# RGB_Video_Output.net
KiCad netlist of a schematic drawn in Altium Designer
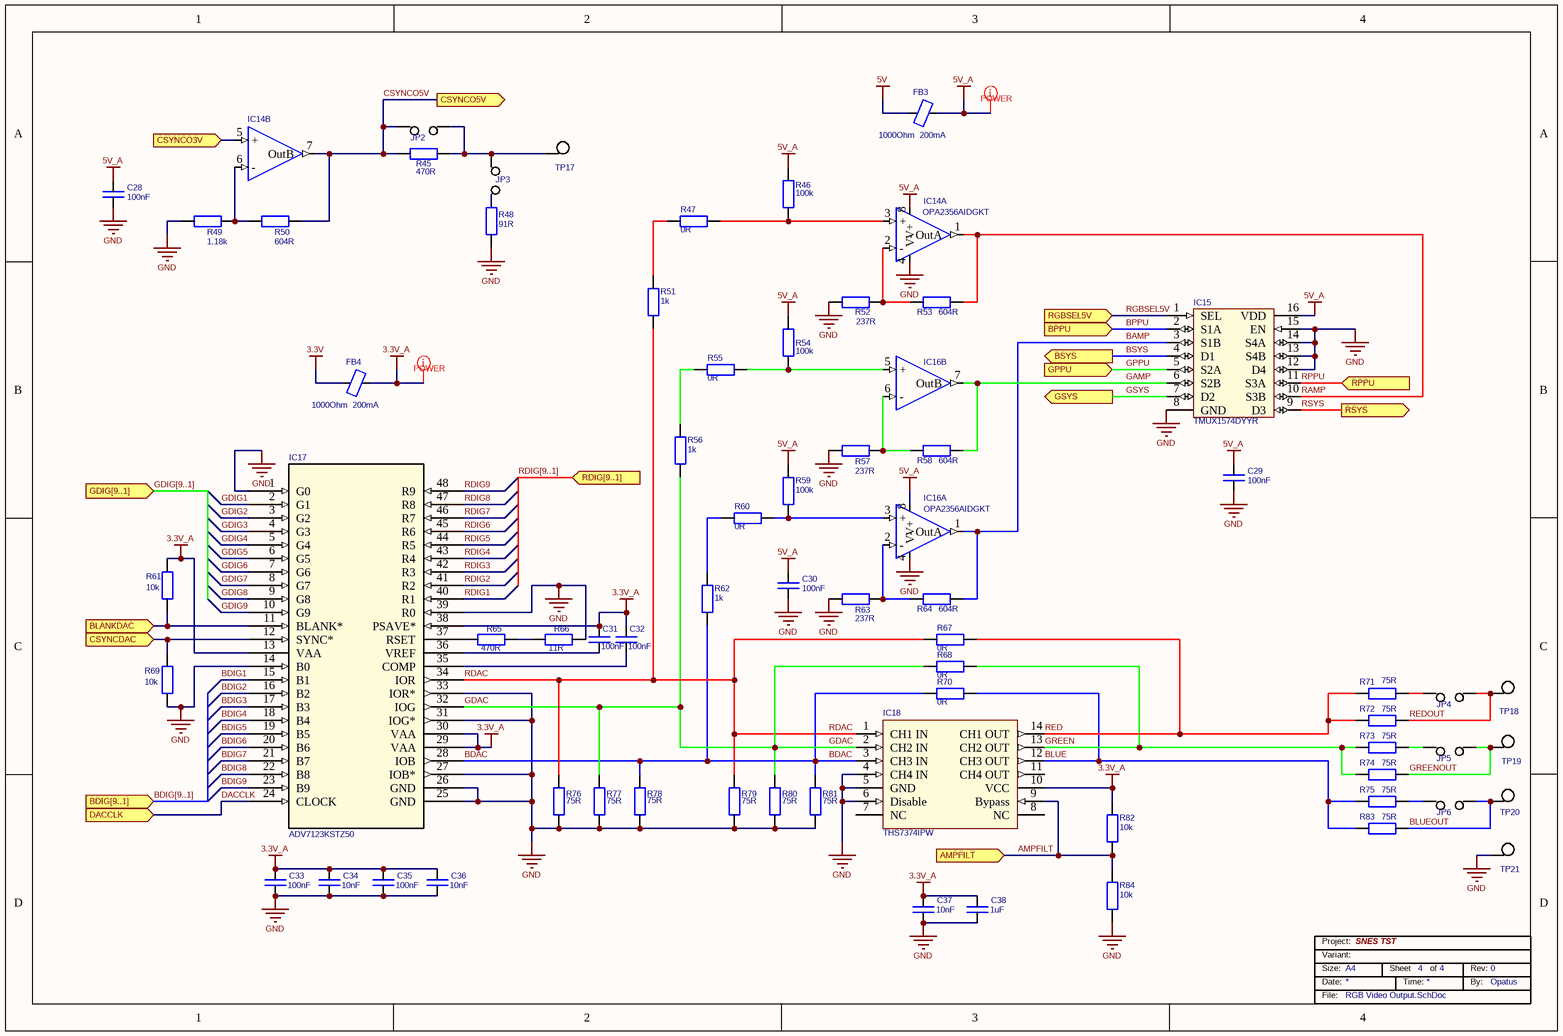
[diagram p0: RGB Video Output.SchDoc]

(export (version "E")
  (design (tool "Eeschema 10.0.6"))
  (components
    (comp (ref "C28")
      (value "100nF")
      (footprint "Cap_0402_Chip")
      (fields
        (field (name "TOLERANCE") "±20%")
        (field (name "Comment") "Ceramic Capacitor 100nF 10V ±20% X7R 0402")
      )
      (libsource (lib "PCB") (part "Capacitor"))
    )
    (comp (ref "C29")
      (value "100nF")
      (footprint "Cap_0402_Chip")
      (fields
        (field (name "TOLERANCE") "±20%")
        (field (name "Comment") "Ceramic Capacitor 100nF 10V ±20% X7R 0402")
      )
      (libsource (lib "PCB") (part "Capacitor"))
    )
    (comp (ref "C30")
      (value "100nF")
      (footprint "Cap_0402_Chip")
      (fields
        (field (name "TOLERANCE") "±20%")
        (field (name "Comment") "Ceramic Capacitor 100nF 10V ±20% X7R 0402")
      )
      (libsource (lib "PCB") (part "Capacitor"))
    )
    (comp (ref "C31")
      (value "100nF")
      (footprint "Cap_0402_Chip")
      (fields
        (field (name "TOLERANCE") "±20%")
        (field (name "Comment") "Ceramic Capacitor 100nF 10V ±20% X7R 0402")
      )
      (libsource (lib "PCB") (part "Capacitor"))
    )
    (comp (ref "C32")
      (value "100nF")
      (footprint "Cap_0402_Chip")
      (fields
        (field (name "TOLERANCE") "±20%")
        (field (name "Comment") "Ceramic Capacitor 100nF 10V ±20% X7R 0402")
      )
      (libsource (lib "PCB") (part "Capacitor"))
    )
    (comp (ref "C33")
      (value "100nF")
      (footprint "Cap_0402_Chip")
      (fields
        (field (name "TOLERANCE") "±20%")
        (field (name "Comment") "Ceramic Capacitor 100nF 10V ±20% X7R 0402")
      )
      (libsource (lib "PCB") (part "Capacitor"))
    )
    (comp (ref "C34")
      (value "10nF")
      (footprint "Cap_0402_Chip")
      (fields
        (field (name "TOLERANCE") "±20%")
        (field (name "Comment") "Ceramic Capacitor 10nF 10V ±20% X7R 0402")
      )
      (libsource (lib "PCB") (part "Capacitor"))
    )
    (comp (ref "C35")
      (value "100nF")
      (footprint "Cap_0402_Chip")
      (fields
        (field (name "TOLERANCE") "±20%")
        (field (name "Comment") "Ceramic Capacitor 100nF 10V ±20% X7R 0402")
      )
      (libsource (lib "PCB") (part "Capacitor"))
    )
    (comp (ref "C36")
      (value "10nF")
      (footprint "Cap_0402_Chip")
      (fields
        (field (name "TOLERANCE") "±20%")
        (field (name "Comment") "Ceramic Capacitor 10nF 10V ±20% X7R 0402")
      )
      (libsource (lib "PCB") (part "Capacitor"))
    )
    (comp (ref "C37")
      (value "10nF")
      (footprint "Cap_0402_Chip")
      (fields
        (field (name "TOLERANCE") "±20%")
        (field (name "Comment") "Ceramic Capacitor 10nF 10V ±20% X7R 0402")
      )
      (libsource (lib "PCB") (part "Capacitor"))
    )
    (comp (ref "C38")
      (value "1uF")
      (footprint "Cap_0603_Chip")
      (fields
        (field (name "TOLERANCE") "±20%")
        (field (name "Comment") "Ceramic Capacitor 1uF 10V ±20% X7R 0603")
      )
      (libsource (lib "PCB") (part "Capacitor"))
    )
    (comp (ref "FB3")
      (value "1000Ohm  200mA")
      (footprint "Ind_0402_Chip")
      (fields (field (name "MANUFACTURER_PART_NUMBER") "MMZ1005S102CT000"))
      (libsource (lib "PCB") (part "Ferrite Bead"))
    )
    (comp (ref "FB4")
      (value "1000Ohm  200mA")
      (footprint "Ind_0402_Chip")
      (fields (field (name "MANUFACTURER_PART_NUMBER") "MMZ1005S102CT000"))
      (libsource (lib "PCB") (part "Ferrite Bead"))
    )
    (comp (ref "IC14")
      (value "OPA2356")
      (footprint "MSOP8")
      (fields (field (name "MANUFACTURER_PART_NUMBER") "OPA2356AIDGKT"))
      (libsource (lib "PCB") (part "OPA2356"))
    )
    (comp (ref "IC15")
      (value "TMUX1574")
      (footprint "SOT-23THIN16")
      (description "SPDT 4 Ch")
      (fields (field (name "MANUFACTURER_PART_NUMBER") "TMUX1574DYYR"))
      (libsource (lib "PCB") (part "TMUX1574"))
    )
    (comp (ref "IC16")
      (value "OPA2356")
      (footprint "MSOP8")
      (fields (field (name "MANUFACTURER_PART_NUMBER") "OPA2356AIDGKT"))
      (libsource (lib "PCB") (part "OPA2356"))
    )
    (comp (ref "IC17")
      (value "ADV7123")
      (footprint "ST_48_ADI")
      (description "10Bit Video DAC")
      (fields
        (field (name "MANUFACTURER_PART_NUMBER") "ADV7123KSTZ50")
        (field (name "COPYRIGHT") "Copyright (C) 2018 Accelerated Designs. All rights reserved")
      )
      (libsource (lib "PCB") (part "ADV7123KSTZ140"))
    )
    (comp (ref "IC18")
      (value "THS7374")
      (footprint "TSSOP14")
      (fields (field (name "MANUFACTURER_PART_NUMBER") "THS7374IPW"))
      (libsource (lib "PCB") (part "THS7374"))
    )
    (comp (ref "JP2") (value "Jumper") (footprint "Jumper") (libsource (lib "PCB") (part "Jumper")))
    (comp (ref "JP3") (value "Jumper") (footprint "Jumper") (libsource (lib "PCB") (part "Jumper")))
    (comp (ref "JP4") (value "Jumper") (footprint "Jumper") (libsource (lib "PCB") (part "Jumper")))
    (comp (ref "JP5") (value "Jumper") (footprint "Jumper") (libsource (lib "PCB") (part "Jumper")))
    (comp (ref "JP6") (value "Jumper") (footprint "Jumper") (libsource (lib "PCB") (part "Jumper")))
    (comp (ref "R45")
      (value "470R")
      (footprint "Res_0603_Chip")
      (fields (field (name "TOLERANCE") "±1%") (field (name "Comment") "Resistor 470R 0603 ±1%"))
      (libsource (lib "") (part "R_3"))
    )
    (comp (ref "R46")
      (value "100k")
      (footprint "Res_0402_Chip")
      (fields (field (name "TOLERANCE") "±1%") (field (name "Comment") "Resistor 100k 0402 ±1%"))
      (libsource (lib "") (part "R_1"))
    )
    (comp (ref "R47")
      (value "0R")
      (footprint "Res_0402_Chip")
      (fields (field (name "Comment") "Resistor 0R 0402 "))
      (libsource (lib "PCB") (part "R"))
    )
    (comp (ref "R48")
      (value "91R")
      (footprint "Res_0603_Chip")
      (fields (field (name "TOLERANCE") "±1%") (field (name "Comment") "Resistor 91R 0603 ±1%"))
      (libsource (lib "") (part "R_1"))
    )
    (comp (ref "R49")
      (value "1.18k")
      (footprint "Res_0402_Chip")
      (fields (field (name "TOLERANCE") "±1%") (field (name "Comment") "Resistor 1.18k 0402 ±1%"))
      (libsource (lib "") (part "R_3"))
    )
    (comp (ref "R50")
      (value "604R")
      (footprint "Res_0402_Chip")
      (fields (field (name "TOLERANCE") "±1%") (field (name "Comment") "Resistor 604R 0402 ±1%"))
      (libsource (lib "PCB") (part "R"))
    )
    (comp (ref "R51")
      (value "1k")
      (footprint "Res_0402_Chip")
      (fields (field (name "TOLERANCE") "±1%") (field (name "Comment") "Resistor 1k 0402 ±1%"))
      (libsource (lib "") (part "R_2"))
    )
    (comp (ref "R52")
      (value "237R")
      (footprint "Res_0402_Chip")
      (fields (field (name "TOLERANCE") "±1%") (field (name "Comment") "Resistor 237R 0402 ±1%"))
      (libsource (lib "") (part "R_3"))
    )
    (comp (ref "R53")
      (value "604R")
      (footprint "Res_0402_Chip")
      (fields (field (name "TOLERANCE") "±1%") (field (name "Comment") "Resistor 604R 0402 ±1%"))
      (libsource (lib "") (part "R_3"))
    )
    (comp (ref "R54")
      (value "100k")
      (footprint "Res_0402_Chip")
      (fields (field (name "TOLERANCE") "±1%") (field (name "Comment") "Resistor 100k 0402 ±1%"))
      (libsource (lib "") (part "R_1"))
    )
    (comp (ref "R55")
      (value "0R")
      (footprint "Res_0402_Chip")
      (fields (field (name "Comment") "Resistor 0R 0402 "))
      (libsource (lib "PCB") (part "R"))
    )
    (comp (ref "R56")
      (value "1k")
      (footprint "Res_0402_Chip")
      (fields (field (name "TOLERANCE") "±1%") (field (name "Comment") "Resistor 1k 0402 ±1%"))
      (libsource (lib "") (part "R_2"))
    )
    (comp (ref "R57")
      (value "237R")
      (footprint "Res_0402_Chip")
      (fields (field (name "TOLERANCE") "±1%") (field (name "Comment") "Resistor 237R 0402 ±1%"))
      (libsource (lib "") (part "R_3"))
    )
    (comp (ref "R58")
      (value "604R")
      (footprint "Res_0402_Chip")
      (fields (field (name "TOLERANCE") "±1%") (field (name "Comment") "Resistor 604R 0402 ±1%"))
      (libsource (lib "PCB") (part "R"))
    )
    (comp (ref "R59")
      (value "100k")
      (footprint "Res_0402_Chip")
      (fields (field (name "TOLERANCE") "±1%") (field (name "Comment") "Resistor 100k 0402 ±1%"))
      (libsource (lib "") (part "R_1"))
    )
    (comp (ref "R60")
      (value "0R")
      (footprint "Res_0402_Chip")
      (fields (field (name "Comment") "Resistor 0R 0402 "))
      (libsource (lib "PCB") (part "R"))
    )
    (comp (ref "R61")
      (value "10k")
      (footprint "Res_0402_Chip")
      (fields (field (name "TOLERANCE") "±1%") (field (name "Comment") "Resistor 10k 0402 ±1%"))
      (libsource (lib "") (part "R_1"))
    )
    (comp (ref "R62")
      (value "1k")
      (footprint "Res_0402_Chip")
      (fields (field (name "TOLERANCE") "±1%") (field (name "Comment") "Resistor 1k 0402 ±1%"))
      (libsource (lib "") (part "R_2"))
    )
    (comp (ref "R63")
      (value "237R")
      (footprint "Res_0402_Chip")
      (fields (field (name "TOLERANCE") "±1%") (field (name "Comment") "Resistor 237R 0402 ±1%"))
      (libsource (lib "PCB") (part "R"))
    )
    (comp (ref "R64")
      (value "604R")
      (footprint "Res_0402_Chip")
      (fields (field (name "TOLERANCE") "±1%") (field (name "Comment") "Resistor 604R 0402 ±1%"))
      (libsource (lib "") (part "R_3"))
    )
    (comp (ref "R65")
      (value "470R")
      (footprint "Res_0402_Chip")
      (fields (field (name "TOLERANCE") "±1%") (field (name "Comment") "Resistor 470R 0402 ±1%"))
      (libsource (lib "") (part "R_3"))
    )
    (comp (ref "R66")
      (value "11R")
      (footprint "Res_0402_Chip")
      (fields (field (name "TOLERANCE") "±1%") (field (name "Comment") "Resistor 11R 0402 ±1%"))
      (libsource (lib "") (part "R_3"))
    )
    (comp (ref "R67")
      (value "0R")
      (footprint "Res_0402_Chip")
      (fields (field (name "Comment") "Resistor 0R 0402 "))
      (libsource (lib "PCB") (part "R"))
    )
    (comp (ref "R68")
      (value "0R")
      (footprint "Res_0402_Chip")
      (fields (field (name "Comment") "Resistor 0R 0402 "))
      (libsource (lib "PCB") (part "R"))
    )
    (comp (ref "R69")
      (value "10k")
      (footprint "Res_0402_Chip")
      (fields (field (name "TOLERANCE") "±1%") (field (name "Comment") "Resistor 10k 0402 ±1%"))
      (libsource (lib "") (part "R_1"))
    )
    (comp (ref "R70")
      (value "0R")
      (footprint "Res_0402_Chip")
      (fields (field (name "Comment") "Resistor 0R 0402 "))
      (libsource (lib "PCB") (part "R"))
    )
    (comp (ref "R71")
      (value "75R")
      (footprint "Res_0603_Chip")
      (fields (field (name "TOLERANCE") "±1%") (field (name "Comment") "Resistor 75R 0603 ±1%"))
      (libsource (lib "") (part "R_3"))
    )
    (comp (ref "R72")
      (value "75R")
      (footprint "Res_0603_Chip")
      (fields (field (name "TOLERANCE") "±1%") (field (name "Comment") "Resistor 75R 0603 ±1%"))
      (libsource (lib "") (part "R_3"))
    )
    (comp (ref "R73")
      (value "75R")
      (footprint "Res_0603_Chip")
      (fields (field (name "TOLERANCE") "±1%") (field (name "Comment") "Resistor 75R 0603 ±1%"))
      (libsource (lib "") (part "R_3"))
    )
    (comp (ref "R74")
      (value "75R")
      (footprint "Res_0603_Chip")
      (fields (field (name "TOLERANCE") "±1%") (field (name "Comment") "Resistor 75R 0603 ±1%"))
      (libsource (lib "") (part "R_3"))
    )
    (comp (ref "R75")
      (value "75R")
      (footprint "Res_0603_Chip")
      (fields (field (name "TOLERANCE") "±1%") (field (name "Comment") "Resistor 75R 0603 ±1%"))
      (libsource (lib "") (part "R_3"))
    )
    (comp (ref "R76")
      (value "75R")
      (footprint "Res_0402_Chip")
      (fields (field (name "TOLERANCE") "±1%") (field (name "Comment") "Resistor 75R 0402 ±1%"))
      (libsource (lib "") (part "R_1"))
    )
    (comp (ref "R77")
      (value "75R")
      (footprint "Res_0402_Chip")
      (fields (field (name "TOLERANCE") "±1%") (field (name "Comment") "Resistor 75R 0402 ±1%"))
      (libsource (lib "") (part "R_1"))
    )
    (comp (ref "R78")
      (value "75R")
      (footprint "Res_0402_Chip")
      (fields (field (name "TOLERANCE") "±1%") (field (name "Comment") "Resistor 75R 0402 ±1%"))
      (libsource (lib "") (part "R_1"))
    )
    (comp (ref "R79")
      (value "75R")
      (footprint "Res_0402_Chip")
      (fields (field (name "TOLERANCE") "±1%") (field (name "Comment") "Resistor 75R 0402 ±1%"))
      (libsource (lib "") (part "R_1"))
    )
    (comp (ref "R80")
      (value "75R")
      (footprint "Res_0402_Chip")
      (fields (field (name "TOLERANCE") "±1%") (field (name "Comment") "Resistor 75R 0402 ±1%"))
      (libsource (lib "") (part "R_1"))
    )
    (comp (ref "R81")
      (value "75R")
      (footprint "Res_0402_Chip")
      (fields (field (name "TOLERANCE") "±1%") (field (name "Comment") "Resistor 75R 0402 ±1%"))
      (libsource (lib "") (part "R_1"))
    )
    (comp (ref "R82")
      (value "10k")
      (footprint "Res_0402_Chip")
      (fields (field (name "TOLERANCE") "±1%") (field (name "Comment") "Resistor 10k 0402 ±1%"))
      (libsource (lib "") (part "R_2"))
    )
    (comp (ref "R83")
      (value "75R")
      (footprint "Res_0603_Chip")
      (fields (field (name "TOLERANCE") "±1%") (field (name "Comment") "Resistor 75R 0603 ±1%"))
      (libsource (lib "") (part "R_3"))
    )
    (comp (ref "R84")
      (value "10k")
      (footprint "Res_0402_Chip")
      (fields (field (name "TOLERANCE") "±1%") (field (name "Comment") "Resistor 10k 0402 ±1%"))
      (libsource (lib "") (part "R_2"))
    )
    (comp (ref "TP17")
      (value "Pin Connector")
      (footprint "Pin Connector Small")
      (libsource (lib "PCB") (part "Pin Connector"))
    )
    (comp (ref "TP18")
      (value "Pin Connector")
      (footprint "Pin Connector Small")
      (libsource (lib "PCB") (part "Pin Connector"))
    )
    (comp (ref "TP19")
      (value "Pin Connector")
      (footprint "Pin Connector Small")
      (libsource (lib "PCB") (part "Pin Connector"))
    )
    (comp (ref "TP20")
      (value "Pin Connector")
      (footprint "Pin Connector Small")
      (libsource (lib "PCB") (part "Pin Connector"))
    )
    (comp (ref "TP21")
      (value "Pin Connector")
      (footprint "Pin Connector Small")
      (libsource (lib "PCB") (part "Pin Connector"))
    )
  )
  (nets
    (net (code "1") (name "/AMPFILT") (class "Default")
      (node (ref "IC18") (pin "9") (pinfunction "Bypass_9") (pintype "input"))
      (node (ref "R82") (pin "2") (pintype "passive"))
      (node (ref "R84") (pin "1") (pintype "passive"))
    )
    (net (code "2") (name "/BAMP") (class "Default")
      (node (ref "IC15") (pin "3") (pinfunction "S1B_3") (pintype "bidirectional"))
      (node (ref "IC16") (pin "1") (pinfunction "OutA_1") (pintype "output"))
      (node (ref "R64") (pin "2") (pintype "passive"))
    )
    (net (code "3") (name "/BDAC") (class "Default")
      (node (ref "IC17") (pin "28") (pinfunction "IOB_28") (pintype "output"))
      (node (ref "IC18") (pin "3") (pinfunction "CH3_IN_3") (pintype "input"))
      (node (ref "R62") (pin "2") (pintype "passive"))
      (node (ref "R70") (pin "2") (pintype "passive"))
      (node (ref "R78") (pin "2") (pintype "passive"))
      (node (ref "R81") (pin "2") (pintype "passive"))
    )
    (net (code "4") (name "/BDIG1") (class "Default")
      (node (ref "IC17") (pin "15") (pinfunction "B1_15") (pintype "input"))
    )
    (net (code "5") (name "/BDIG2") (class "Default")
      (node (ref "IC17") (pin "16") (pinfunction "B2_16") (pintype "input"))
    )
    (net (code "6") (name "/BDIG3") (class "Default")
      (node (ref "IC17") (pin "17") (pinfunction "B3_17") (pintype "input"))
    )
    (net (code "7") (name "/BDIG4") (class "Default")
      (node (ref "IC17") (pin "18") (pinfunction "B4_18") (pintype "input"))
    )
    (net (code "8") (name "/BDIG5") (class "Default")
      (node (ref "IC17") (pin "19") (pinfunction "B5_19") (pintype "input"))
    )
    (net (code "9") (name "/BDIG6") (class "Default")
      (node (ref "IC17") (pin "20") (pinfunction "B6_20") (pintype "input"))
    )
    (net (code "10") (name "/BDIG7") (class "Default")
      (node (ref "IC17") (pin "21") (pinfunction "B7_21") (pintype "input"))
    )
    (net (code "11") (name "/BDIG8") (class "Default")
      (node (ref "IC17") (pin "22") (pinfunction "B8_22") (pintype "input"))
    )
    (net (code "12") (name "/BDIG9") (class "Default")
      (node (ref "IC17") (pin "23") (pinfunction "B9_23") (pintype "input"))
    )
    (net (code "14") (name "/BLANKDAC") (class "Default")
      (node (ref "IC17") (pin "11") (pinfunction "BLANK*_11") (pintype "input"))
      (node (ref "R61") (pin "1") (pintype "passive"))
    )
    (net (code "15") (name "/BLUE") (class "Default")
      (node (ref "IC18") (pin "12") (pinfunction "CH3_OUT_12") (pintype "output"))
      (node (ref "R70") (pin "1") (pintype "passive"))
      (node (ref "R75") (pin "1") (pintype "passive"))
      (node (ref "R83") (pin "1") (pintype "passive"))
    )
    (net (code "16") (name "/BLUEOUT") (class "Default")
      (node (ref "JP6") (pin "1") (pinfunction "0_1") (pintype "passive"))
      (node (ref "R83") (pin "2") (pintype "passive"))
      (node (ref "TP20") (pin "1") (pinfunction "0_1") (pintype "passive"))
    )
    (net (code "17") (name "/BPPU") (class "Default")
      (node (ref "IC15") (pin "2") (pinfunction "S1A_2") (pintype "bidirectional"))
    )
    (net (code "18") (name "/BSYS") (class "Default")
      (node (ref "IC15") (pin "4") (pinfunction "D1_4") (pintype "bidirectional"))
    )
    (net (code "19") (name "/CSYNCDAC") (class "Default")
      (node (ref "IC17") (pin "12") (pinfunction "SYNC*_12") (pintype "input"))
      (node (ref "R69") (pin "2") (pintype "passive"))
    )
    (net (code "20") (name "/CSYNCO3V") (class "Default")
      (node (ref "IC14") (pin "5") (pinfunction "+_5") (pintype "input"))
    )
    (net (code "21") (name "/CSYNCO5V") (class "Default")
      (node (ref "IC14") (pin "7") (pinfunction "OutB_7") (pintype "output"))
      (node (ref "JP2") (pin "2") (pinfunction "0_2") (pintype "passive"))
      (node (ref "R45") (pin "1") (pintype "passive"))
      (node (ref "R50") (pin "1") (pintype "passive"))
    )
    (net (code "22") (name "/DACCLK") (class "Default")
      (node (ref "IC17") (pin "24") (pinfunction "CLOCK_24") (pintype "input"))
    )
    (net (code "23") (name "/GAMP") (class "Default")
      (node (ref "IC15") (pin "6") (pinfunction "S2B_6") (pintype "bidirectional"))
      (node (ref "IC16") (pin "7") (pinfunction "OutB_7") (pintype "output"))
      (node (ref "R58") (pin "1") (pintype "passive"))
    )
    (net (code "24") (name "/GDAC") (class "Default")
      (node (ref "IC17") (pin "32") (pinfunction "IOG_32") (pintype "output"))
      (node (ref "IC18") (pin "2") (pinfunction "CH2_IN_2") (pintype "input"))
      (node (ref "R56") (pin "2") (pintype "passive"))
      (node (ref "R68") (pin "2") (pintype "passive"))
      (node (ref "R77") (pin "2") (pintype "passive"))
      (node (ref "R80") (pin "2") (pintype "passive"))
    )
    (net (code "25") (name "/GDIG1") (class "Default")
      (node (ref "IC17") (pin "2") (pinfunction "G1_2") (pintype "input"))
    )
    (net (code "26") (name "/GDIG2") (class "Default")
      (node (ref "IC17") (pin "3") (pinfunction "G2_3") (pintype "input"))
    )
    (net (code "27") (name "/GDIG3") (class "Default")
      (node (ref "IC17") (pin "4") (pinfunction "G3_4") (pintype "input"))
    )
    (net (code "28") (name "/GDIG4") (class "Default")
      (node (ref "IC17") (pin "5") (pinfunction "G4_5") (pintype "input"))
    )
    (net (code "29") (name "/GDIG5") (class "Default")
      (node (ref "IC17") (pin "6") (pinfunction "G5_6") (pintype "input"))
    )
    (net (code "30") (name "/GDIG6") (class "Default")
      (node (ref "IC17") (pin "7") (pinfunction "G6_7") (pintype "input"))
    )
    (net (code "31") (name "/GDIG7") (class "Default")
      (node (ref "IC17") (pin "8") (pinfunction "G7_8") (pintype "input"))
    )
    (net (code "32") (name "/GDIG8") (class "Default")
      (node (ref "IC17") (pin "9") (pinfunction "G8_9") (pintype "input"))
    )
    (net (code "33") (name "/GDIG9") (class "Default")
      (node (ref "IC17") (pin "10") (pinfunction "G9_10") (pintype "input"))
    )
    (net (code "35") (name "/GPPU") (class "Default")
      (node (ref "IC15") (pin "5") (pinfunction "S2A_5") (pintype "bidirectional"))
    )
    (net (code "36") (name "/GREEN") (class "Default")
      (node (ref "IC18") (pin "13") (pinfunction "CH2_OUT_13") (pintype "output"))
      (node (ref "R68") (pin "1") (pintype "passive"))
      (node (ref "R73") (pin "1") (pintype "passive"))
      (node (ref "R74") (pin "1") (pintype "passive"))
    )
    (net (code "37") (name "/GREENOUT") (class "Default")
      (node (ref "JP5") (pin "1") (pinfunction "0_1") (pintype "passive"))
      (node (ref "R74") (pin "2") (pintype "passive"))
      (node (ref "TP19") (pin "1") (pinfunction "0_1") (pintype "passive"))
    )
    (net (code "38") (name "/GSYS") (class "Default")
      (node (ref "IC15") (pin "7") (pinfunction "D2_7") (pintype "bidirectional"))
    )
    (net (code "39") (name "/RAMP") (class "Default")
      (node (ref "IC14") (pin "1") (pinfunction "OutA_1") (pintype "output"))
      (node (ref "IC15") (pin "10") (pinfunction "S3B_10") (pintype "bidirectional"))
      (node (ref "R53") (pin "2") (pintype "passive"))
    )
    (net (code "40") (name "/RDAC") (class "Default")
      (node (ref "IC17") (pin "34") (pinfunction "IOR_34") (pintype "output"))
      (node (ref "IC18") (pin "1") (pinfunction "CH1_IN_1") (pintype "input"))
      (node (ref "R51") (pin "2") (pintype "passive"))
      (node (ref "R67") (pin "2") (pintype "passive"))
      (node (ref "R76") (pin "2") (pintype "passive"))
      (node (ref "R79") (pin "2") (pintype "passive"))
    )
    (net (code "41") (name "/RDIG1") (class "Default")
      (node (ref "IC17") (pin "40") (pinfunction "R1_40") (pintype "input"))
    )
    (net (code "42") (name "/RDIG2") (class "Default")
      (node (ref "IC17") (pin "41") (pinfunction "R2_41") (pintype "input"))
    )
    (net (code "43") (name "/RDIG3") (class "Default")
      (node (ref "IC17") (pin "42") (pinfunction "R3_42") (pintype "input"))
    )
    (net (code "44") (name "/RDIG4") (class "Default")
      (node (ref "IC17") (pin "43") (pinfunction "R4_43") (pintype "input"))
    )
    (net (code "45") (name "/RDIG5") (class "Default")
      (node (ref "IC17") (pin "44") (pinfunction "R5_44") (pintype "input"))
    )
    (net (code "46") (name "/RDIG6") (class "Default")
      (node (ref "IC17") (pin "45") (pinfunction "R6_45") (pintype "input"))
    )
    (net (code "47") (name "/RDIG7") (class "Default")
      (node (ref "IC17") (pin "46") (pinfunction "R7_46") (pintype "input"))
    )
    (net (code "48") (name "/RDIG8") (class "Default")
      (node (ref "IC17") (pin "47") (pinfunction "R8_47") (pintype "input"))
    )
    (net (code "49") (name "/RDIG9") (class "Default")
      (node (ref "IC17") (pin "48") (pinfunction "R9_48") (pintype "input"))
    )
    (net (code "51") (name "/RED") (class "Default")
      (node (ref "IC18") (pin "14") (pinfunction "CH1_OUT_14") (pintype "output"))
      (node (ref "R67") (pin "1") (pintype "passive"))
      (node (ref "R71") (pin "1") (pintype "passive"))
      (node (ref "R72") (pin "1") (pintype "passive"))
    )
    (net (code "52") (name "/REDOUT") (class "Default")
      (node (ref "JP4") (pin "1") (pinfunction "0_1") (pintype "passive"))
      (node (ref "R72") (pin "2") (pintype "passive"))
      (node (ref "TP18") (pin "1") (pinfunction "0_1") (pintype "passive"))
    )
    (net (code "53") (name "/RGBSEL5V") (class "Default")
      (node (ref "IC15") (pin "1") (pinfunction "SEL_1") (pintype "input"))
    )
    (net (code "54") (name "/RPPU") (class "Default")
      (node (ref "IC15") (pin "11") (pinfunction "S3A_11") (pintype "bidirectional"))
    )
    (net (code "55") (name "/RSYS") (class "Default")
      (node (ref "IC15") (pin "9") (pinfunction "D3_9") (pintype "bidirectional"))
    )
    (net (code "56") (name "3.3V") (class "Default") (node (ref "FB4") (pin "1") (pintype "passive")))
    (net (code "57") (name "3.3V_A") (class "Default")
      (node (ref "C31") (pin "1") (pintype "passive"))
      (node (ref "C32") (pin "1") (pintype "passive"))
      (node (ref "C33") (pin "2") (pintype "passive"))
      (node (ref "C34") (pin "2") (pintype "passive"))
      (node (ref "C35") (pin "2") (pintype "passive"))
      (node (ref "C36") (pin "2") (pintype "passive"))
      (node (ref "C37") (pin "2") (pintype "passive"))
      (node (ref "C38") (pin "2") (pintype "passive"))
      (node (ref "FB4") (pin "2") (pintype "passive"))
      (node (ref "IC17") (pin "13") (pinfunction "VAA_13") (pintype "power_in"))
      (node (ref "IC17") (pin "29") (pinfunction "VAA_29") (pintype "power_in"))
      (node (ref "IC17") (pin "30") (pinfunction "VAA_30") (pintype "power_in"))
      (node (ref "IC17") (pin "38") (pinfunction "PSAVE*_38") (pintype "input"))
      (node (ref "IC18") (pin "10") (pinfunction "VCC_10") (pintype "power_in"))
      (node (ref "R61") (pin "2") (pintype "passive"))
      (node (ref "R82") (pin "1") (pintype "passive"))
    )
    (net (code "58") (name "5V") (class "Default") (node (ref "FB3") (pin "1") (pintype "passive")))
    (net (code "59") (name "5V_A") (class "Default")
      (node (ref "C28") (pin "1") (pintype "passive"))
      (node (ref "C29") (pin "1") (pintype "passive"))
      (node (ref "C30") (pin "1") (pintype "passive"))
      (node (ref "FB3") (pin "2") (pintype "passive"))
      (node (ref "IC14") (pin "8") (pinfunction "V+_8") (pintype "power_in"))
      (node (ref "IC15") (pin "16") (pinfunction "VDD_16") (pintype "power_in"))
      (node (ref "IC16") (pin "8") (pinfunction "V+_8") (pintype "power_in"))
      (node (ref "R46") (pin "2") (pintype "passive"))
      (node (ref "R54") (pin "2") (pintype "passive"))
      (node (ref "R59") (pin "2") (pintype "passive"))
    )
    (net (code "60") (name "GND") (class "Default")
      (node (ref "C28") (pin "2") (pintype "passive"))
      (node (ref "C29") (pin "2") (pintype "passive"))
      (node (ref "C30") (pin "2") (pintype "passive"))
      (node (ref "C33") (pin "1") (pintype "passive"))
      (node (ref "C34") (pin "1") (pintype "passive"))
      (node (ref "C35") (pin "1") (pintype "passive"))
      (node (ref "C36") (pin "1") (pintype "passive"))
      (node (ref "C37") (pin "1") (pintype "passive"))
      (node (ref "C38") (pin "1") (pintype "passive"))
      (node (ref "IC14") (pin "4") (pinfunction "V-_4") (pintype "power_in"))
      (node (ref "IC15") (pin "12") (pinfunction "D4_12") (pintype "bidirectional"))
      (node (ref "IC15") (pin "13") (pinfunction "S4B_13") (pintype "bidirectional"))
      (node (ref "IC15") (pin "14") (pinfunction "S4A_14") (pintype "bidirectional"))
      (node (ref "IC15") (pin "15") (pinfunction "EN_15") (pintype "input"))
      (node (ref "IC15") (pin "8") (pinfunction "GND_8") (pintype "power_in"))
      (node (ref "IC16") (pin "4") (pinfunction "V-_4") (pintype "power_in"))
      (node (ref "IC17") (pin "1") (pinfunction "G0_1") (pintype "input"))
      (node (ref "IC17") (pin "14") (pinfunction "B0_14") (pintype "input"))
      (node (ref "IC17") (pin "25") (pinfunction "GND_25") (pintype "power_in"))
      (node (ref "IC17") (pin "26") (pinfunction "GND_26") (pintype "power_in"))
      (node (ref "IC17") (pin "27") (pinfunction "IOB*_27") (pintype "output"))
      (node (ref "IC17") (pin "31") (pinfunction "IOG*_31") (pintype "output"))
      (node (ref "IC17") (pin "33") (pinfunction "IOR*_33") (pintype "output"))
      (node (ref "IC17") (pin "39") (pinfunction "R0_39") (pintype "input"))
      (node (ref "IC18") (pin "4") (pinfunction "CH4_IN_4") (pintype "input"))
      (node (ref "IC18") (pin "5") (pinfunction "GND_5") (pintype "power_in"))
      (node (ref "IC18") (pin "6") (pinfunction "Disable_6") (pintype "input"))
      (node (ref "R48") (pin "1") (pintype "passive"))
      (node (ref "R49") (pin "1") (pintype "passive"))
      (node (ref "R52") (pin "1") (pintype "passive"))
      (node (ref "R57") (pin "1") (pintype "passive"))
      (node (ref "R63") (pin "2") (pintype "passive"))
      (node (ref "R66") (pin "2") (pintype "passive"))
      (node (ref "R69") (pin "1") (pintype "passive"))
      (node (ref "R76") (pin "1") (pintype "passive"))
      (node (ref "R77") (pin "1") (pintype "passive"))
      (node (ref "R78") (pin "1") (pintype "passive"))
      (node (ref "R79") (pin "1") (pintype "passive"))
      (node (ref "R80") (pin "1") (pintype "passive"))
      (node (ref "R81") (pin "1") (pintype "passive"))
      (node (ref "R84") (pin "2") (pintype "passive"))
      (node (ref "TP21") (pin "1") (pinfunction "0_1") (pintype "passive"))
    )
    (net (code "61") (name "Net-(IC14A-+)") (class "Default")
      (node (ref "IC14") (pin "3") (pinfunction "+_3") (pintype "input"))
      (node (ref "R46") (pin "1") (pintype "passive"))
      (node (ref "R47") (pin "1") (pintype "passive"))
    )
    (net (code "62") (name "Net-(IC14A--)") (class "Default")
      (node (ref "IC14") (pin "2") (pinfunction "-_2") (pintype "input"))
      (node (ref "R52") (pin "2") (pintype "passive"))
      (node (ref "R53") (pin "1") (pintype "passive"))
    )
    (net (code "63") (name "Net-(IC14B--)") (class "Default")
      (node (ref "IC14") (pin "6") (pinfunction "-_6") (pintype "input"))
      (node (ref "R49") (pin "2") (pintype "passive"))
      (node (ref "R50") (pin "2") (pintype "passive"))
    )
    (net (code "64") (name "Net-(IC16A-+)") (class "Default")
      (node (ref "IC16") (pin "3") (pinfunction "+_3") (pintype "input"))
      (node (ref "R59") (pin "1") (pintype "passive"))
      (node (ref "R60") (pin "1") (pintype "passive"))
    )
    (net (code "65") (name "Net-(IC16A--)") (class "Default")
      (node (ref "IC16") (pin "2") (pinfunction "-_2") (pintype "input"))
      (node (ref "R63") (pin "1") (pintype "passive"))
      (node (ref "R64") (pin "1") (pintype "passive"))
    )
    (net (code "66") (name "Net-(IC16B-+)") (class "Default")
      (node (ref "IC16") (pin "5") (pinfunction "+_5") (pintype "input"))
      (node (ref "R54") (pin "1") (pintype "passive"))
      (node (ref "R55") (pin "1") (pintype "passive"))
    )
    (net (code "67") (name "Net-(IC16B--)") (class "Default")
      (node (ref "IC16") (pin "6") (pinfunction "-_6") (pintype "input"))
      (node (ref "R57") (pin "2") (pintype "passive"))
      (node (ref "R58") (pin "2") (pintype "passive"))
    )
    (net (code "68") (name "Net-(IC17-COMP)") (class "Default")
      (node (ref "C32") (pin "2") (pintype "passive"))
      (node (ref "IC17") (pin "35") (pinfunction "COMP_35") (pintype "passive"))
    )
    (net (code "69") (name "Net-(IC17-RSET)") (class "Default")
      (node (ref "IC17") (pin "37") (pinfunction "RSET_37") (pintype "passive"))
      (node (ref "R65") (pin "1") (pintype "passive"))
    )
    (net (code "70") (name "Net-(IC17-VREF)") (class "Default")
      (node (ref "C31") (pin "2") (pintype "passive"))
      (node (ref "IC17") (pin "36") (pinfunction "VREF_36") (pintype "passive"))
    )
    (net (code "71") (name "Net-(JP3-0-Pad2)") (class "Default")
      (node (ref "JP3") (pin "2") (pinfunction "0_2") (pintype "passive"))
      (node (ref "R48") (pin "2") (pintype "passive"))
    )
    (net (code "72") (name "Net-(JP4-0-Pad2)") (class "Default")
      (node (ref "JP4") (pin "2") (pinfunction "0_2") (pintype "passive"))
      (node (ref "R71") (pin "2") (pintype "passive"))
    )
    (net (code "73") (name "Net-(JP5-0-Pad2)") (class "Default")
      (node (ref "JP5") (pin "2") (pinfunction "0_2") (pintype "passive"))
      (node (ref "R73") (pin "2") (pintype "passive"))
    )
    (net (code "74") (name "Net-(JP6-0-Pad2)") (class "Default")
      (node (ref "JP6") (pin "2") (pinfunction "0_2") (pintype "passive"))
      (node (ref "R75") (pin "2") (pintype "passive"))
    )
    (net (code "75") (name "Net-(R47-Pad2)") (class "Default")
      (node (ref "R47") (pin "2") (pintype "passive"))
      (node (ref "R51") (pin "1") (pintype "passive"))
    )
    (net (code "76") (name "Net-(R55-Pad2)") (class "Default")
      (node (ref "R55") (pin "2") (pintype "passive"))
      (node (ref "R56") (pin "1") (pintype "passive"))
    )
    (net (code "77") (name "Net-(R60-Pad2)") (class "Default")
      (node (ref "R60") (pin "2") (pintype "passive"))
      (node (ref "R62") (pin "1") (pintype "passive"))
    )
    (net (code "78") (name "Net-(R65-Pad2)") (class "Default")
      (node (ref "R65") (pin "2") (pintype "passive"))
      (node (ref "R66") (pin "1") (pintype "passive"))
    )
    (net (code "79") (name "Net-(TP17-0)") (class "Default")
      (node (ref "JP2") (pin "1") (pinfunction "0_1") (pintype "passive"))
      (node (ref "JP3") (pin "1") (pinfunction "0_1") (pintype "passive"))
      (node (ref "R45") (pin "2") (pintype "passive"))
      (node (ref "TP17") (pin "1") (pinfunction "0_1") (pintype "passive"))
    )
    (net (code "80") (name "unconnected-(IC18-CH4_OUT-Pad11)") (class "Default")
      (node (ref "IC18") (pin "11") (pinfunction "CH4_OUT_11") (pintype "output"))
    )
    (net (code "81") (name "unconnected-(IC18-NC-Pad7)") (class "Default")
      (node (ref "IC18") (pin "7") (pinfunction "NC_7") (pintype "passive"))
    )
    (net (code "82") (name "unconnected-(IC18-NC-Pad8)") (class "Default")
      (node (ref "IC18") (pin "8") (pinfunction "NC_8") (pintype "passive"))
    )
  )
)
